# design.net
KiCad netlist of a schematic drawn in Altium Designer
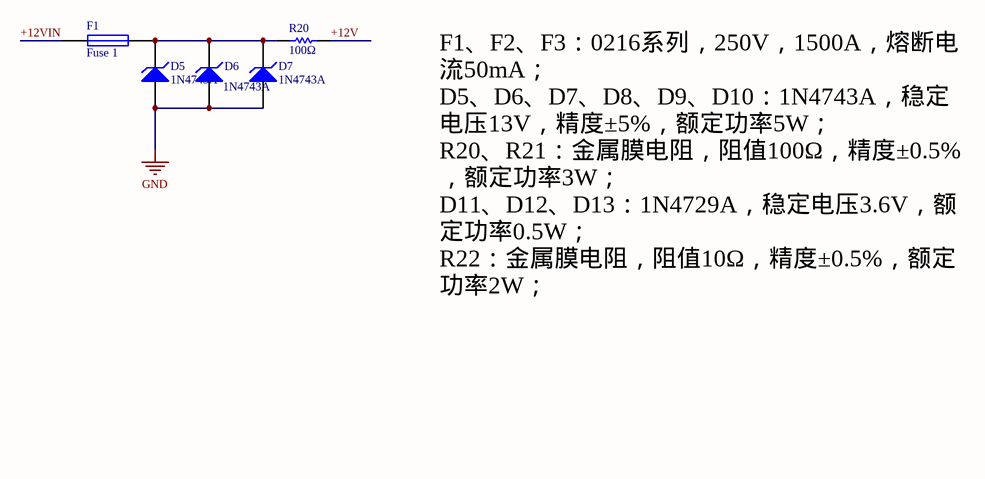
[diagram p0: 齐纳安全栅.SchDoc]

(export (version "E")
  (design (tool "Eeschema 10.0.6"))
  (components
    (comp (ref "D5")
      (value "1N4743A")
      (footprint "DO-41")
      (description "Zener Diode")
      (fields (field (name "PUBLISHER") "Altium Limited"))
      (libsource (lib "Miscellaneous Devices") (part "D Zener"))
    )
    (comp (ref "D6")
      (value "1N4743A")
      (footprint "DO-41")
      (description "Zener Diode")
      (fields (field (name "PUBLISHER") "Altium Limited"))
      (libsource (lib "Miscellaneous Devices") (part "D Zener"))
    )
    (comp (ref "D7")
      (value "1N4743A")
      (footprint "DO-41")
      (description "Zener Diode")
      (fields (field (name "PUBLISHER") "Altium Limited"))
      (libsource (lib "Miscellaneous Devices") (part "D Zener"))
    )
    (comp (ref "F1")
      (value "Fuse 1")
      (footprint "PIN-W2/E2.8")
      (description "Fuse")
      (fields (field (name "PUBLISHER") "Altium Limited"))
      (libsource (lib "Miscellaneous Devices") (part "Fuse 1"))
    )
    (comp (ref "R20")
      (value "100Ω")
      (footprint "AXIAL-0.3")
      (description "Resistor")
      (fields (field (name "PUBLISHER") "Altium Limited"))
      (libsource (lib "Miscellaneous Devices") (part "Res1"))
    )
  )
  (nets
    (net (code "1") (name "/+12V") (class "Default")
      (node (ref "R20") (pin "2") (pinfunction "2_2") (pintype "passive"))
    )
    (net (code "2") (name "/+12VIN") (class "Default")
      (node (ref "F1") (pin "1") (pinfunction "1_1") (pintype "passive"))
    )
    (net (code "3") (name "GND") (class "Default")
      (node (ref "D5") (pin "1") (pinfunction "A_1") (pintype "passive"))
      (node (ref "D6") (pin "1") (pinfunction "A_1") (pintype "passive"))
      (node (ref "D7") (pin "1") (pinfunction "A_1") (pintype "passive"))
    )
    (net (code "4") (name "Net-(D5-K)") (class "Default")
      (node (ref "D5") (pin "2") (pinfunction "K_2") (pintype "passive"))
      (node (ref "D6") (pin "2") (pinfunction "K_2") (pintype "passive"))
      (node (ref "D7") (pin "2") (pinfunction "K_2") (pintype "passive"))
      (node (ref "F1") (pin "2") (pinfunction "2_2") (pintype "passive"))
      (node (ref "R20") (pin "1") (pinfunction "1_1") (pintype "passive"))
    )
  )
)
